# Power.net
KiCad netlist of a schematic drawn in Altium Designer
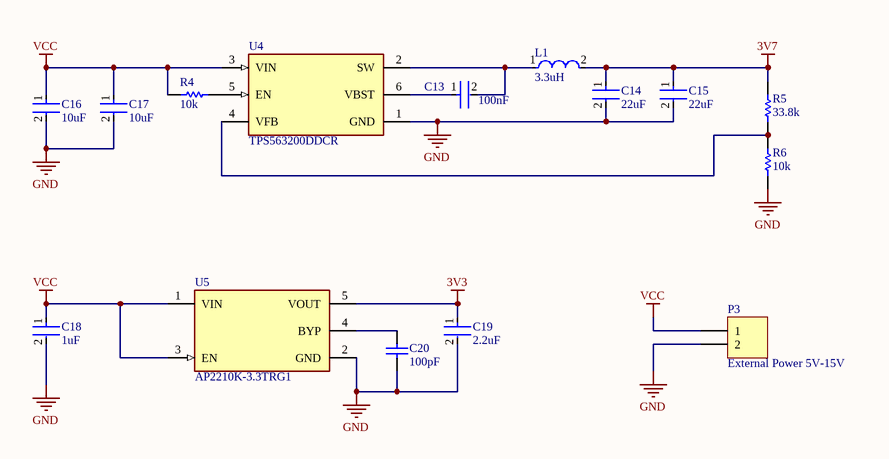
[diagram p0: Power.SchDoc]

(export (version "E")
  (design (tool "Eeschema 10.0.6"))
  (components
    (comp (ref "C13")
      (value "100nF")
      (footprint "FP-CL21-IPC_C")
      (description "CL21 Series 0805 100nF 50V ±10% Tolerance X7R Multilayer Ceramic Chip Capacitor")
      (fields (field (name "TOLERANCE") "10%") (field (name "VOLTAGE") "50V"))
      (libsource (lib "Altium Content Vault") (part "b4654b650e69147ec39a6b967a45e02"))
    )
    (comp (ref "C14")
      (value "22uF")
      (footprint "FP-CL21-IPC_A")
      (description "CL21 Series 0805 22uF 6.3V ±20% Tolerance X5R Multilayer Ceramic Chip Capacitor")
      (fields (field (name "TOLERANCE") "20%"))
      (libsource (lib "Altium Content Vault") (part "b4654b650e69147ec39a6b967a45e02"))
    )
    (comp (ref "C15")
      (value "22uF")
      (footprint "FP-CL21-IPC_A")
      (description "CL21 Series 0805 22uF 6.3V ±20% Tolerance X5R Multilayer Ceramic Chip Capacitor")
      (fields (field (name "TOLERANCE") "20%"))
      (libsource (lib "Altium Content Vault") (part "b4654b650e69147ec39a6b967a45e02"))
    )
    (comp (ref "C16")
      (value "10uF")
      (footprint "FP-CL21-IPC_B")
      (description "CL21 Series 0805 10uF 16V ±10% Tolerance X5R Multilayer Ceramic Chip Capacitor")
      (fields (field (name "VOLTAGE") "16V") (field (name "TOLERANCE") "10%"))
      (libsource (lib "Altium Content Vault") (part "b4654b650e69147ec39a6b967a45e02"))
    )
    (comp (ref "C17")
      (value "10uF")
      (footprint "FP-CL21-IPC_B")
      (description "CL21 Series 0805 10uF 16V ±10% Tolerance X5R Multilayer Ceramic Chip Capacitor")
      (fields (field (name "VOLTAGE") "16V") (field (name "TOLERANCE") "10%"))
      (libsource (lib "Altium Content Vault") (part "b4654b650e69147ec39a6b967a45e02"))
    )
    (comp (ref "C18")
      (value "1uF")
      (footprint "FP-CL21-IPC_C")
      (description "CL21 Series 0805 1uF 50V ±10% Tolerance X7R Multilayer Ceramic Chip Capacitor")
      (fields (field (name "TOLERANCE") "10%"))
      (libsource (lib "Altium Content Vault") (part "b4654b650e69147ec39a6b967a45e02"))
    )
    (comp (ref "C19")
      (value "2.2uF")
      (footprint "FP-GRM21B-0_15-IPC_A")
      (description "Chip Multilayer Ceramic Capacitors for General Purpose, 0805, 2.2uF, X7R, 15%, 10%, 25V")
      (fields (field (name "TOLERANCE") "10%"))
      (libsource (lib "Altium Content Vault") (part "b4654b650e69147ec39a6b967a45e02"))
    )
    (comp (ref "C20")
      (value "100pF")
      (footprint "CAPC2013X145X48NL20T23")
      (fields (field (name "PART NUMBER") "VJ0805A101JXGAT5Z") (field (name "MANUFACTURER") "Vitramon"))
      (libsource (lib "Altium Content Vault") (part "CAP"))
    )
    (comp (ref "L1")
      (value "3.3uH")
      (footprint "FP-SRP4020TA-MFG")
      (description "FIXED IND 3.3UH 3.5A 76 MOHM SMD")
      (fields
        (field (name "OCTOPART") "https://octopart.com/srp4020ta-3r3m-bourns-47300338")
        (field (name "MANUFACTURER") "Bourns")
      )
      (libsource (lib "Altium Content Vault") (part "725321dda6339637d4d059423bc1c3c"))
    )
    (comp (ref "P3")
      (value "External Power 5V-15V")
      (footprint "HDR1X2")
      (description "Header, 2-Pin")
      (fields (field (name "PUBLISHER") "Altium Limited"))
      (libsource (lib "Miscellaneous Connectors") (part "Header 2"))
    )
    (comp (ref "R4")
      (value "10k")
      (footprint "RESC2013X60X35NL10T20")
      (description "Chip Resistor, 10 KOhm, +/- 1%, 0.125 W, -55 to 155 degC, 0805 (2012 Metric), RoHS, Tape and Reel")
      (fields (field (name "MANUFACTURER") "Yageo"))
      (libsource (lib "Altium Content Vault") (part "RES-2"))
    )
    (comp (ref "R5")
      (value "33.8k")
      (footprint "RESC2013X60X35ML10T20")
      (fields (field (name "MANUFACTURER") "Yageo") (field (name "PART NUMBER") "RC0805FR-0738K3L"))
      (libsource (lib "Altium Content Vault") (part "RES"))
    )
    (comp (ref "R6")
      (value "10k")
      (footprint "RESC2013X60X35NL10T20")
      (description "Chip Resistor, 10 KOhm, +/- 1%, 0.125 W, -55 to 155 degC, 0805 (2012 Metric), RoHS, Tape and Reel")
      (fields (field (name "MANUFACTURER") "Yageo"))
      (libsource (lib "Altium Content Vault") (part "RES-2"))
    )
    (comp (ref "U4")
      (value "TPS563200DDCR")
      (footprint "FP-DDC0006A-MFG")
      (description "IC REG BUCK ADJ 3A TSOT23-6")
      (libsource (lib "Altium Content Vault") (part "31d0a13bcb823f7fa58c78a9b473f81"))
    )
    (comp (ref "U5")
      (value "AP2210K-3.3TRG1")
      (footprint "FP-SOT25-MFG")
      (description "IC REG LINEAR 3.3V 300MA SOT23-5")
      (fields
        (field (name "MANUFACTURER") "Diodes")
        (field (name "OCTOPART") "https://octopart.com/ap2210k-3.3trg1-diodes+inc.-30954630")
      )
      (libsource (lib "Altium Content Vault") (part "c51eb117839baecd597f0ee1e447120"))
    )
  )
  (nets
    (net (code "1") (name "3V3") (class "Default")
      (node (ref "C19") (pin "1") (pinfunction "1_1") (pintype "passive"))
      (node (ref "U5") (pin "5") (pinfunction "VOUT_5") (pintype "power_in"))
    )
    (net (code "2") (name "3V7") (class "Default")
      (node (ref "C14") (pin "1") (pinfunction "1_1") (pintype "passive"))
      (node (ref "C15") (pin "1") (pinfunction "1_1") (pintype "passive"))
      (node (ref "L1") (pin "2") (pinfunction "2_2") (pintype "passive"))
      (node (ref "R5") (pin "2") (pinfunction "2_2") (pintype "passive"))
    )
    (net (code "3") (name "GND") (class "Default")
      (node (ref "C14") (pin "2") (pinfunction "2_2") (pintype "passive"))
      (node (ref "C15") (pin "2") (pinfunction "2_2") (pintype "passive"))
      (node (ref "C16") (pin "2") (pinfunction "2_2") (pintype "passive"))
      (node (ref "C17") (pin "2") (pinfunction "2_2") (pintype "passive"))
      (node (ref "C18") (pin "2") (pinfunction "2_2") (pintype "passive"))
      (node (ref "C19") (pin "2") (pinfunction "2_2") (pintype "passive"))
      (node (ref "C20") (pin "1") (pinfunction "1_1") (pintype "passive"))
      (node (ref "P3") (pin "2") (pinfunction "2_2") (pintype "passive"))
      (node (ref "R6") (pin "1") (pinfunction "1_1") (pintype "passive"))
      (node (ref "U4") (pin "1") (pinfunction "GND_1") (pintype "power_in"))
      (node (ref "U5") (pin "2") (pinfunction "GND_2") (pintype "power_in"))
    )
    (net (code "4") (name "Net-(U4-EN)") (class "Default")
      (node (ref "R4") (pin "2") (pinfunction "2_2") (pintype "passive"))
      (node (ref "U4") (pin "5") (pinfunction "EN_5") (pintype "input"))
    )
    (net (code "5") (name "Net-(U4-SW)") (class "Default")
      (node (ref "C13") (pin "2") (pinfunction "2_2") (pintype "passive"))
      (node (ref "L1") (pin "1") (pinfunction "1_1") (pintype "passive"))
      (node (ref "U4") (pin "2") (pinfunction "SW_2") (pintype "passive"))
    )
    (net (code "6") (name "Net-(U4-VBST)") (class "Default")
      (node (ref "C13") (pin "1") (pinfunction "1_1") (pintype "passive"))
      (node (ref "U4") (pin "6") (pinfunction "VBST_6") (pintype "passive"))
    )
    (net (code "7") (name "Net-(U4-VFB)") (class "Default")
      (node (ref "R5") (pin "1") (pinfunction "1_1") (pintype "passive"))
      (node (ref "R6") (pin "2") (pinfunction "2_2") (pintype "passive"))
      (node (ref "U4") (pin "4") (pinfunction "VFB_4") (pintype "passive"))
    )
    (net (code "8") (name "Net-(U5-BYP)") (class "Default")
      (node (ref "C20") (pin "2") (pinfunction "2_2") (pintype "passive"))
      (node (ref "U5") (pin "4") (pinfunction "BYP_4") (pintype "passive"))
    )
    (net (code "9") (name "VCC") (class "Default")
      (node (ref "C16") (pin "1") (pinfunction "1_1") (pintype "passive"))
      (node (ref "C17") (pin "1") (pinfunction "1_1") (pintype "passive"))
      (node (ref "C18") (pin "1") (pinfunction "1_1") (pintype "passive"))
      (node (ref "P3") (pin "1") (pinfunction "1_1") (pintype "passive"))
      (node (ref "R4") (pin "1") (pinfunction "1_1") (pintype "passive"))
      (node (ref "U4") (pin "3") (pinfunction "VIN_3") (pintype "input"))
      (node (ref "U5") (pin "1") (pinfunction "VIN_1") (pintype "power_in"))
      (node (ref "U5") (pin "3") (pinfunction "EN_3") (pintype "input"))
    )
  )
)
